# 1-Schematic.net
KiCad netlist of a schematic drawn in EasyEDA
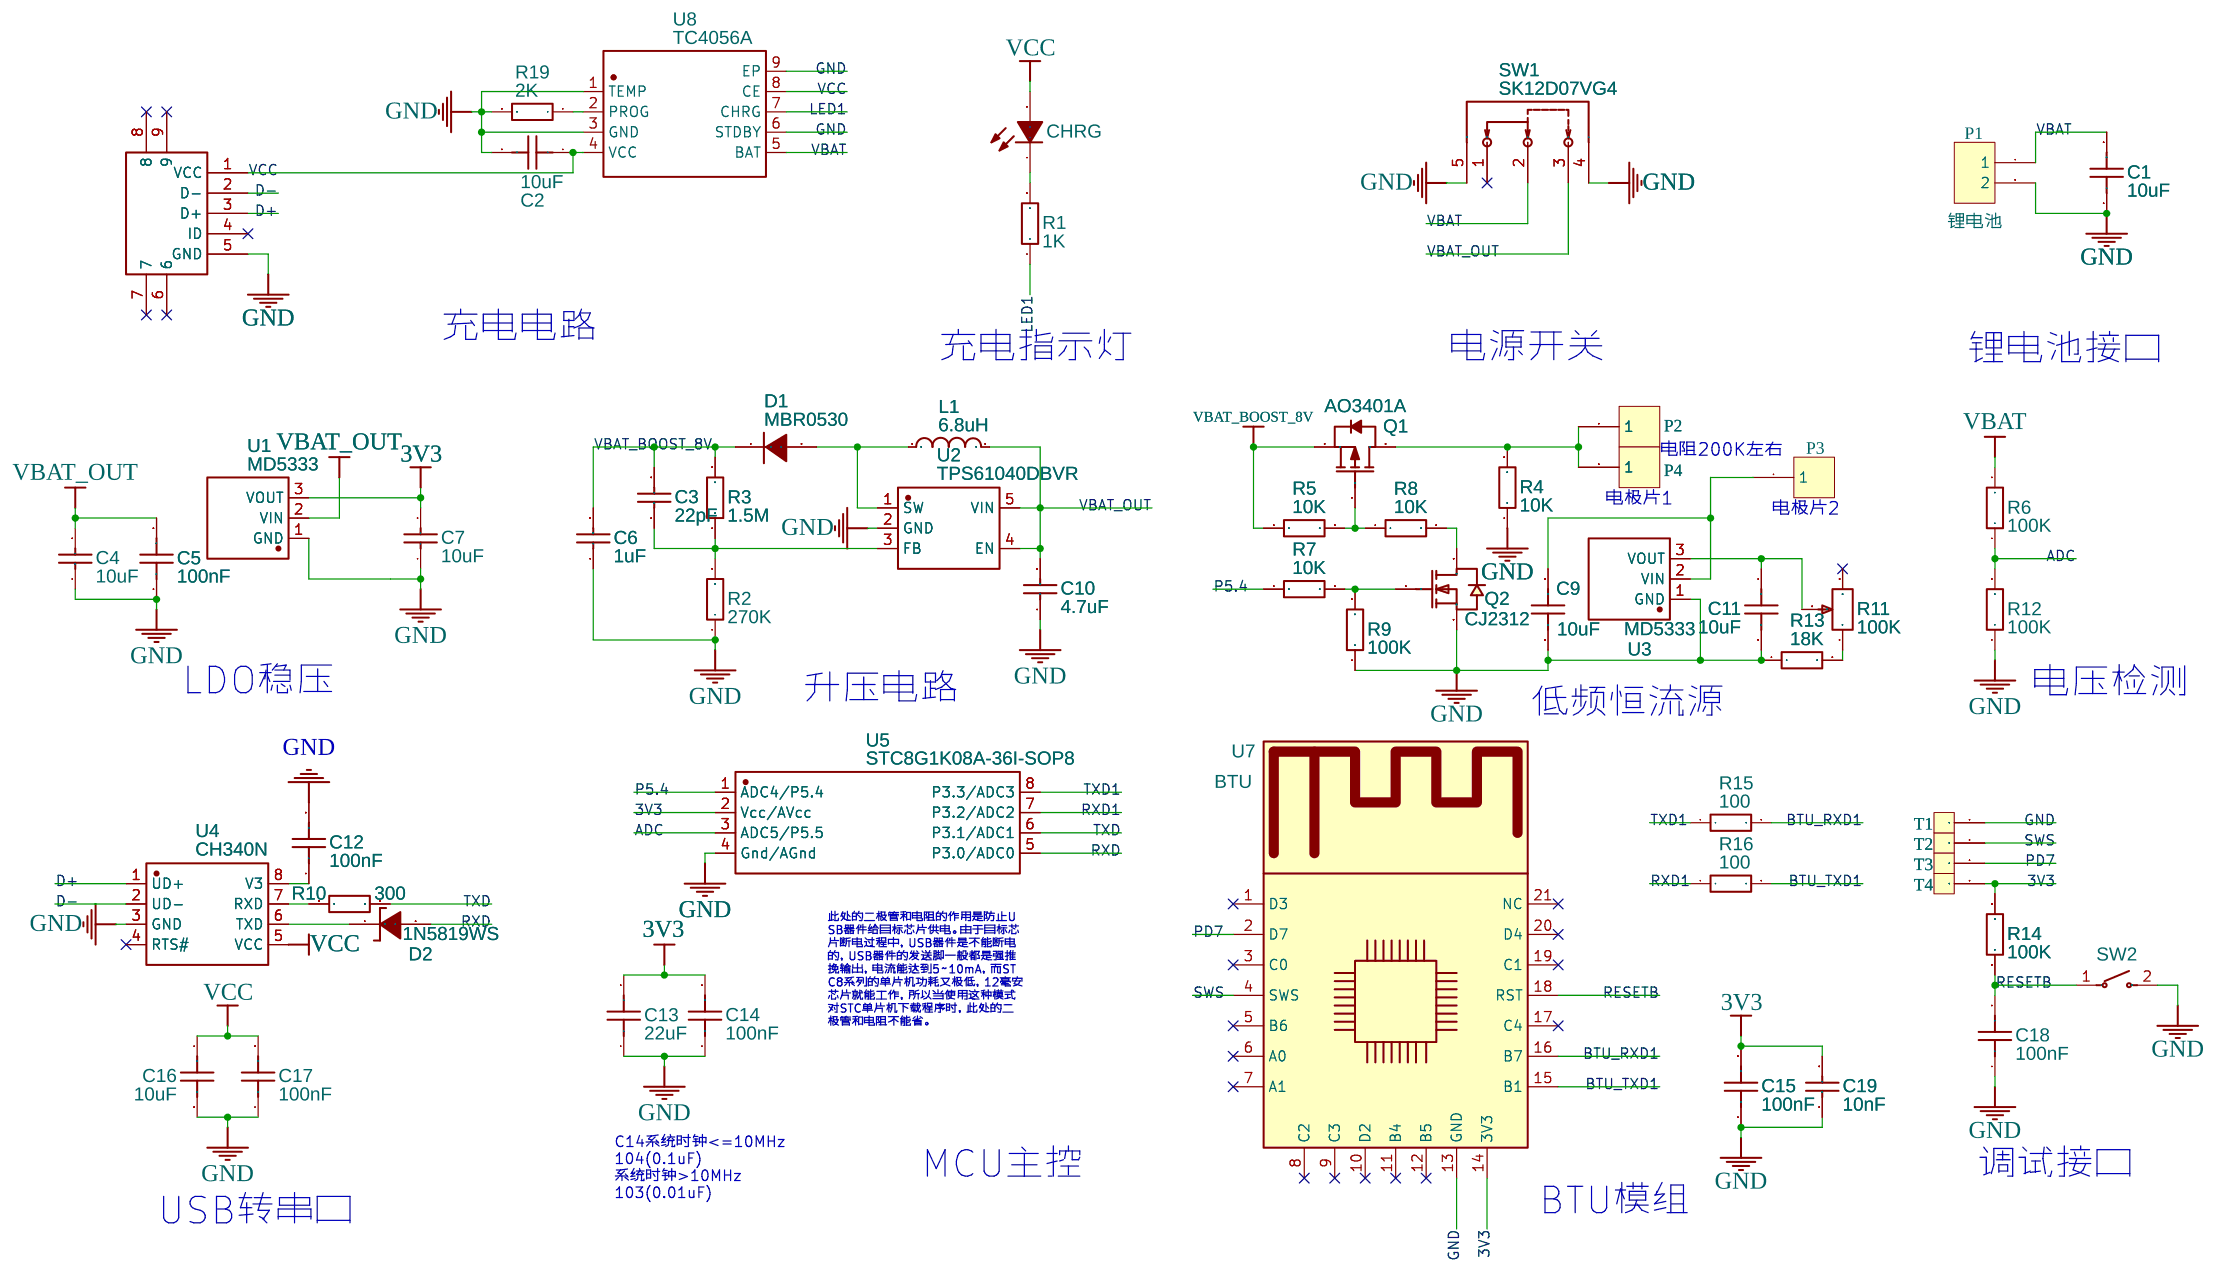
[diagram p0: schematic sheet]

(export (version "E")
  (design (tool "Eeschema 10.0.6"))
  (components
    (comp (ref "C1")
      (value "10uF")
      (fields
        (field (name "BOM_Manufacturer Part") "CL10A106KP8NNNC")
        (field (name "BOM_Supplier Part") "C19702")
      )
      (libsource (lib "") (part "CL10A106KP8NNNC"))
    )
    (comp (ref "C2")
      (value "10uF")
      (fields
        (field (name "BOM_Manufacturer Part") "CL10A106KP8NNNC")
        (field (name "BOM_Supplier Part") "C19702")
      )
      (libsource (lib "") (part "CL10A106KP8NNNC_2"))
    )
    (comp (ref "C3")
      (value "22pF")
      (fields
        (field (name "BOM_Manufacturer Part") "CC0603JRNPO9BN220")
        (field (name "BOM_Supplier Part") "C105620")
      )
      (libsource (lib "") (part "CC0603JRNPO9BN220"))
    )
    (comp (ref "C4")
      (value "10uF")
      (fields
        (field (name "BOM_Manufacturer Part") "CC0603MRX5R6BB106")
        (field (name "BOM_Supplier Part") "C109453")
      )
      (libsource (lib "") (part "CC0603MRX5R6BB106"))
    )
    (comp (ref "C5")
      (value "100nF")
      (fields
        (field (name "BOM_Manufacturer Part") "0603F104Z500")
        (field (name "BOM_Supplier Part") "C83060")
      )
      (libsource (lib "") (part "0603F104Z500"))
    )
    (comp (ref "C6")
      (value "1uF")
      (fields
        (field (name "BOM_Manufacturer Part") "CL10A105KO8NNNC")
        (field (name "BOM_Supplier Part") "C1592")
      )
      (libsource (lib "") (part "CL10A105KO8NNNC"))
    )
    (comp (ref "C7")
      (value "10uF")
      (fields
        (field (name "BOM_Manufacturer Part") "CC0603MRX5R6BB106")
        (field (name "BOM_Supplier Part") "C109453")
      )
      (libsource (lib "") (part "CC0603MRX5R6BB106"))
    )
    (comp (ref "C9")
      (value "10uF")
      (fields
        (field (name "BOM_Manufacturer Part") "CL10A106KP8NNNC")
        (field (name "BOM_Supplier Part") "C19702")
      )
      (libsource (lib "") (part "CL10A106KP8NNNC_1"))
    )
    (comp (ref "C10")
      (value "4.7uF")
      (fields
        (field (name "BOM_Manufacturer Part") "CL10A475KP8NNNC")
        (field (name "BOM_Supplier Part") "C1705")
      )
      (libsource (lib "") (part "CL10A475KP8NNNC"))
    )
    (comp (ref "C11")
      (value "10uF")
      (fields
        (field (name "BOM_Manufacturer Part") "CL10A106KP8NNNC")
        (field (name "BOM_Supplier Part") "C19702")
      )
      (libsource (lib "") (part "CL10A106KP8NNNC_1"))
    )
    (comp (ref "C12")
      (value "100nF")
      (fields
        (field (name "BOM_Manufacturer Part") "CC0603KRX7R9BB104")
        (field (name "BOM_Supplier Part") "C14663")
      )
      (libsource (lib "") (part "CC0603KRX7R9BB104"))
    )
    (comp (ref "C13")
      (value "22uF")
      (fields
        (field (name "BOM_Manufacturer Part") "CL10A226MQ8NRNC")
        (field (name "BOM_Supplier Part") "C59461")
      )
      (libsource (lib "") (part "CL10A226MQ8NRNC"))
    )
    (comp (ref "C14")
      (value "100nF")
      (fields
        (field (name "BOM_Manufacturer Part") "CC0603KRX7R9BB104")
        (field (name "BOM_Supplier Part") "C14663")
      )
      (libsource (lib "") (part "CC0603KRX7R9BB104"))
    )
    (comp (ref "C15")
      (value "100nF")
      (fields
        (field (name "BOM_Manufacturer Part") "CC0603KRX7R9BB104")
        (field (name "BOM_Supplier Part") "C14663")
      )
      (libsource (lib "") (part "CC0603KRX7R9BB104"))
    )
    (comp (ref "C16")
      (value "10uF")
      (fields
        (field (name "BOM_Manufacturer Part") "CL10A106KP8NNNC")
        (field (name "BOM_Supplier Part") "C19702")
      )
      (libsource (lib "") (part "CL10A106KP8NNNC_1"))
    )
    (comp (ref "C17")
      (value "100nF")
      (fields
        (field (name "BOM_Manufacturer Part") "CC0603KRX7R9BB104")
        (field (name "BOM_Supplier Part") "C14663")
      )
      (libsource (lib "") (part "CC0603KRX7R9BB104"))
    )
    (comp (ref "C18")
      (value "100nF")
      (fields
        (field (name "BOM_Manufacturer Part") "CC0603KRX7R9BB104")
        (field (name "BOM_Supplier Part") "C14663")
      )
      (libsource (lib "") (part "CC0603KRX7R9BB104"))
    )
    (comp (ref "C19")
      (value "10nF")
      (fields
        (field (name "BOM_Manufacturer Part") "CC0603KRX7R9BB103")
        (field (name "BOM_Supplier Part") "C100042")
      )
      (libsource (lib "") (part "CC0603KRX7R9BB103"))
    )
    (comp (ref "CHRG")
      (value "19-21SURC/S530-A2/TR8")
      (fields (field (name "BOM_Supplier Part") "C72045"))
      (libsource (lib "") (part "19-21SURC/S530-A2/TR8"))
    )
    (comp (ref "D1")
      (value "MBR0530")
      (fields (field (name "BOM_Supplier Part") "C475718"))
      (libsource (lib "") (part "MBR0530_C475718"))
    )
    (comp (ref "D2")
      (value "1N5819WS")
      (fields (field (name "BOM_Supplier Part") "C191023"))
      (libsource (lib "") (part "1N5819WS"))
    )
    (comp (ref "L1")
      (value "6.8uH")
      (fields
        (field (name "BOM_Manufacturer Part") "CDRH3D23NP-6R8PC")
        (field (name "BOM_Supplier Part") "C323532")
      )
      (libsource (lib "") (part "CDRH3D23NP-6R8PC"))
    )
    (comp (ref "P1") (value "锂电池") (libsource (lib "") (part "Unknown_1010_-650")))
    (comp (ref "P2") (value "CON1") (libsource (lib "") (part "Unknown_825_-520")))
    (comp (ref "P3") (value "CON1") (libsource (lib "") (part "Unknown_911_-495")))
    (comp (ref "P4") (value "CON1") (libsource (lib "") (part "Unknown_825_-500")))
    (comp (ref "Q1")
      (value "AO3401A")
      (fields (field (name "BOM_Supplier Part") "C15127"))
      (libsource (lib "") (part "AO3401A"))
    )
    (comp (ref "Q2")
      (value "CJ2312")
      (fields (field (name "BOM_Supplier Part") "C23521"))
      (libsource (lib "") (part "CJ2312"))
    )
    (comp (ref "R1")
      (value "1K")
      (fields
        (field (name "BOM_Manufacturer Part") "RS-03K1001FT")
        (field (name "BOM_Supplier Part") "C115325")
      )
      (libsource (lib "") (part "RS-03K1001FT"))
    )
    (comp (ref "R2")
      (value "270K")
      (fields
        (field (name "BOM_Manufacturer Part") "0603WAF2703T5E")
        (field (name "BOM_Supplier Part") "C22965")
      )
      (libsource (lib "") (part "0603WAF2703T5E"))
    )
    (comp (ref "R3")
      (value "1.5M")
      (fields
        (field (name "BOM_Manufacturer Part") "0603WAF1504T5E")
        (field (name "BOM_Supplier Part") "C4172")
      )
      (libsource (lib "") (part "0603WAF1504T5E"))
    )
    (comp (ref "R4")
      (value "10K")
      (fields
        (field (name "BOM_Manufacturer Part") "RS-03K103JT")
        (field (name "BOM_Supplier Part") "C73809")
      )
      (libsource (lib "") (part "RS-03K103JT_1"))
    )
    (comp (ref "R5")
      (value "10K")
      (fields
        (field (name "BOM_Manufacturer Part") "RS-03K103JT")
        (field (name "BOM_Supplier Part") "C73809")
      )
      (libsource (lib "") (part "RS-03K103JT"))
    )
    (comp (ref "R6")
      (value "100K")
      (fields
        (field (name "BOM_Manufacturer Part") "RC0603FR-07100KL")
        (field (name "BOM_Supplier Part") "C14675")
      )
      (libsource (lib "") (part "RC0603FR-07100KL"))
    )
    (comp (ref "R7")
      (value "10K")
      (fields
        (field (name "BOM_Manufacturer Part") "RS-03K103JT")
        (field (name "BOM_Supplier Part") "C73809")
      )
      (libsource (lib "") (part "RS-03K103JT"))
    )
    (comp (ref "R8")
      (value "10K")
      (fields
        (field (name "BOM_Manufacturer Part") "RS-03K103JT")
        (field (name "BOM_Supplier Part") "C73809")
      )
      (libsource (lib "") (part "RS-03K103JT"))
    )
    (comp (ref "R9")
      (value "100K")
      (fields
        (field (name "BOM_Manufacturer Part") "RC0603FR-07100KL")
        (field (name "BOM_Supplier Part") "C14675")
      )
      (libsource (lib "") (part "RC0603FR-07100KL"))
    )
    (comp (ref "R10")
      (value "300")
      (fields
        (field (name "BOM_Manufacturer Part") "0603WAF3000T5E")
        (field (name "BOM_Supplier Part") "C23025")
      )
      (libsource (lib "") (part "0603WAF3000T5E"))
    )
    (comp (ref "R11")
      (value "100K")
      (fields
        (field (name "BOM_Manufacturer Part") "VG039NCHXTB104")
        (field (name "BOM_Supplier Part") "C128545")
      )
      (libsource (lib "") (part "VG039NCHXTB104"))
    )
    (comp (ref "R12")
      (value "100K")
      (fields
        (field (name "BOM_Manufacturer Part") "RC0603FR-07100KL")
        (field (name "BOM_Supplier Part") "C14675")
      )
      (libsource (lib "") (part "RC0603FR-07100KL"))
    )
    (comp (ref "R13")
      (value "18K")
      (fields
        (field (name "BOM_Manufacturer Part") "WR06X1502FTL")
        (field (name "BOM_Supplier Part") "C163863")
      )
      (libsource (lib "") (part "WR06X1502FTL"))
    )
    (comp (ref "R14")
      (value "100K")
      (fields
        (field (name "BOM_Manufacturer Part") "RC0603FR-07100KL")
        (field (name "BOM_Supplier Part") "C14675")
      )
      (libsource (lib "") (part "RC0603FR-07100KL"))
    )
    (comp (ref "R15")
      (value "100")
      (fields
        (field (name "BOM_Manufacturer Part") "0603WAJ0101T5E")
        (field (name "BOM_Supplier Part") "C25201")
      )
      (libsource (lib "") (part "0603WAJ0101T5E"))
    )
    (comp (ref "R16")
      (value "100")
      (fields
        (field (name "BOM_Manufacturer Part") "0603WAJ0101T5E")
        (field (name "BOM_Supplier Part") "C25201")
      )
      (libsource (lib "") (part "0603WAJ0101T5E"))
    )
    (comp (ref "R19")
      (value "2K")
      (fields
        (field (name "BOM_Manufacturer Part") "0603WAJ0202T5E")
        (field (name "BOM_Supplier Part") "C25590")
      )
      (libsource (lib "") (part "0603WAJ0202T5E"))
    )
    (comp (ref "SW1")
      (value "SK12D07VG4")
      (fields (field (name "BOM_Supplier Part") "C393937"))
      (libsource (lib "") (part "SK12D07VG4"))
    )
    (comp (ref "SW2")
      (value "TS-1088R-02026")
      (fields (field (name "BOM_Supplier Part") "C455280"))
      (libsource (lib "") (part "TS-1088R-02026"))
    )
    (comp (ref "T1") (value "TP") (libsource (lib "") (part "Unknown_985_-315")))
    (comp (ref "T2") (value "TP") (libsource (lib "") (part "Unknown_985_-305")))
    (comp (ref "T3") (value "TP") (libsource (lib "") (part "Unknown_985_-295")))
    (comp (ref "T4") (value "TP") (libsource (lib "") (part "Unknown_985_-285")))
    (comp (ref "U1")
      (value "MD5333")
      (fields (field (name "BOM_Supplier Part") "C2827936"))
      (libsource (lib "") (part "MD5333"))
    )
    (comp (ref "U2")
      (value "TPS61040DBVR")
      (fields (field (name "BOM_Supplier Part") "C7722"))
      (libsource (lib "") (part "TPS61040DBVR"))
    )
    (comp (ref "U3")
      (value "MD5333")
      (fields (field (name "BOM_Supplier Part") "C2827936"))
      (libsource (lib "") (part "MD5333"))
    )
    (comp (ref "U4")
      (value "CH340N")
      (fields (field (name "BOM_Supplier Part") "C506813"))
      (libsource (lib "") (part "CH340N"))
    )
    (comp (ref "U5")
      (value "STC8G1K08A-36I-SOP8")
      (fields (field (name "BOM_Supplier Part") "C915663"))
      (libsource (lib "") (part "STC8G1K08A-36I-SOP8"))
    )
    (comp (ref "U7") (value "BTU") (libsource (lib "") (part "BTU")))
    (comp (ref "U8")
      (value "TC4056A")
      (fields (field (name "BOM_Supplier Part") "C84051"))
      (libsource (lib "") (part "TC4056A"))
    )
    (comp (ref "USB1")
      (value "U254-051T-4BH23-S2S")
      (fields (field (name "BOM_Supplier Part") "C319163"))
      (libsource (lib "") (part "U254-051T-4BH23-S2S"))
    )
  )
  (nets
    (net (code "1") (name "/ADC") (class "Default")
      (node (ref "R12") (pin "2") (pinfunction "2_2") (pintype "unspecified"))
      (node (ref "R6") (pin "1") (pinfunction "1_1") (pintype "unspecified"))
      (node (ref "U5") (pin "3") (pinfunction "ADC5/P5.5_3") (pintype "unspecified"))
    )
    (net (code "2") (name "/BTU_RXD1") (class "Default")
      (node (ref "R15") (pin "2") (pinfunction "2_2") (pintype "input"))
      (node (ref "U7") (pin "16") (pinfunction "B7_16") (pintype "unspecified"))
    )
    (net (code "3") (name "/BTU_TXD1") (class "Default")
      (node (ref "R16") (pin "2") (pinfunction "2_2") (pintype "input"))
      (node (ref "U7") (pin "15") (pinfunction "B1_15") (pintype "unspecified"))
    )
    (net (code "4") (name "/D+") (class "Default")
      (node (ref "U4") (pin "1") (pinfunction "UD+_1") (pintype "unspecified"))
      (node (ref "USB1") (pin "3") (pinfunction "D+_3") (pintype "unspecified"))
    )
    (net (code "5") (name "/D-") (class "Default")
      (node (ref "U4") (pin "2") (pinfunction "UD-_2") (pintype "unspecified"))
      (node (ref "USB1") (pin "2") (pinfunction "D-_2") (pintype "unspecified"))
    )
    (net (code "6") (name "/LED1") (class "Default")
      (node (ref "R1") (pin "1") (pinfunction "1_1") (pintype "input"))
      (node (ref "U8") (pin "7") (pinfunction "CHRG_7") (pintype "unspecified"))
    )
    (net (code "7") (name "/P5.4") (class "Default")
      (node (ref "R7") (pin "1") (pinfunction "1_1") (pintype "input"))
      (node (ref "U5") (pin "1") (pinfunction "ADC4/P5.4_1") (pintype "unspecified"))
    )
    (net (code "8") (name "/PD7") (class "Default")
      (node (ref "T3") (pin "1") (pinfunction "1_1") (pintype "unspecified"))
      (node (ref "U7") (pin "2") (pinfunction "D7_2") (pintype "unspecified"))
    )
    (net (code "9") (name "/RESETB") (class "Default")
      (node (ref "C18") (pin "2") (pinfunction "2_2") (pintype "unspecified"))
      (node (ref "R14") (pin "1") (pinfunction "1_1") (pintype "unspecified"))
      (node (ref "SW2") (pin "1") (pinfunction "1_1") (pintype "unspecified"))
      (node (ref "U7") (pin "18") (pinfunction "RST_18") (pintype "unspecified"))
    )
    (net (code "10") (name "/RXD") (class "Default")
      (node (ref "D2") (pin "2") (pinfunction "A_2") (pintype "unspecified"))
      (node (ref "U5") (pin "5") (pinfunction "P3.0/ADC0_5") (pintype "unspecified"))
    )
    (net (code "11") (name "/RXD1") (class "Default")
      (node (ref "R16") (pin "1") (pinfunction "1_1") (pintype "input"))
      (node (ref "U5") (pin "7") (pinfunction "P3.2/ADC2_7") (pintype "unspecified"))
    )
    (net (code "12") (name "/SWS") (class "Default")
      (node (ref "T2") (pin "1") (pinfunction "1_1") (pintype "unspecified"))
      (node (ref "U7") (pin "4") (pinfunction "SWS_4") (pintype "unspecified"))
    )
    (net (code "13") (name "/TXD") (class "Default")
      (node (ref "R10") (pin "2") (pinfunction "2_2") (pintype "input"))
      (node (ref "U5") (pin "6") (pinfunction "P3.1/ADC1_6") (pintype "unspecified"))
    )
    (net (code "14") (name "/TXD1") (class "Default")
      (node (ref "R15") (pin "1") (pinfunction "1_1") (pintype "input"))
      (node (ref "U5") (pin "8") (pinfunction "P3.3/ADC3_8") (pintype "unspecified"))
    )
    (net (code "15") (name "3V3") (class "Default")
      (node (ref "C13") (pin "2") (pinfunction "2_2") (pintype "unspecified"))
      (node (ref "C14") (pin "2") (pinfunction "2_2") (pintype "unspecified"))
      (node (ref "C15") (pin "2") (pinfunction "2_2") (pintype "unspecified"))
      (node (ref "C19") (pin "2") (pinfunction "2_2") (pintype "input"))
      (node (ref "C7") (pin "2") (pinfunction "2_2") (pintype "input"))
      (node (ref "R14") (pin "2") (pinfunction "2_2") (pintype "unspecified"))
      (node (ref "T4") (pin "1") (pinfunction "1_1") (pintype "unspecified"))
      (node (ref "U1") (pin "3") (pinfunction "VOUT_3") (pintype "unspecified"))
      (node (ref "U5") (pin "2") (pinfunction "Vcc/AVcc_2") (pintype "unspecified"))
      (node (ref "U7") (pin "14") (pinfunction "3V3_14") (pintype "unspecified"))
    )
    (net (code "16") (name "GND") (class "Default")
      (node (ref "C1") (pin "1") (pinfunction "1_1") (pintype "unspecified"))
      (node (ref "C10") (pin "1") (pinfunction "1_1") (pintype "input"))
      (node (ref "C11") (pin "2") (pinfunction "2_2") (pintype "unspecified"))
      (node (ref "C12") (pin "2") (pinfunction "2_2") (pintype "unspecified"))
      (node (ref "C13") (pin "1") (pinfunction "1_1") (pintype "unspecified"))
      (node (ref "C14") (pin "1") (pinfunction "1_1") (pintype "unspecified"))
      (node (ref "C15") (pin "1") (pinfunction "1_1") (pintype "unspecified"))
      (node (ref "C16") (pin "2") (pinfunction "2_2") (pintype "unspecified"))
      (node (ref "C17") (pin "1") (pinfunction "1_1") (pintype "unspecified"))
      (node (ref "C18") (pin "1") (pinfunction "1_1") (pintype "unspecified"))
      (node (ref "C19") (pin "1") (pinfunction "1_1") (pintype "input"))
      (node (ref "C2") (pin "2") (pinfunction "2_2") (pintype "unspecified"))
      (node (ref "C4") (pin "1") (pinfunction "1_1") (pintype "input"))
      (node (ref "C5") (pin "1") (pinfunction "1_1") (pintype "unspecified"))
      (node (ref "C6") (pin "1") (pinfunction "1_1") (pintype "input"))
      (node (ref "C7") (pin "1") (pinfunction "1_1") (pintype "input"))
      (node (ref "C9") (pin "2") (pinfunction "2_2") (pintype "unspecified"))
      (node (ref "P1") (pin "2") (pinfunction "2_2") (pintype "unspecified"))
      (node (ref "Q2") (pin "2") (pinfunction "S_2") (pintype "unspecified"))
      (node (ref "R12") (pin "1") (pinfunction "1_1") (pintype "unspecified"))
      (node (ref "R13") (pin "1") (pinfunction "1_1") (pintype "unspecified"))
      (node (ref "R19") (pin "2") (pinfunction "2_2") (pintype "input"))
      (node (ref "R2") (pin "1") (pinfunction "1_1") (pintype "input"))
      (node (ref "R4") (pin "1") (pinfunction "1_1") (pintype "input"))
      (node (ref "R9") (pin "1") (pinfunction "1_1") (pintype "unspecified"))
      (node (ref "SW1") (pin "4") (pinfunction "4_4") (pintype "unspecified"))
      (node (ref "SW1") (pin "5") (pinfunction "5_5") (pintype "unspecified"))
      (node (ref "SW2") (pin "2") (pinfunction "2_2") (pintype "unspecified"))
      (node (ref "T1") (pin "1") (pinfunction "1_1") (pintype "unspecified"))
      (node (ref "U1") (pin "1") (pinfunction "GND_1") (pintype "unspecified"))
      (node (ref "U2") (pin "2") (pinfunction "GND_2") (pintype "unspecified"))
      (node (ref "U3") (pin "1") (pinfunction "GND_1") (pintype "unspecified"))
      (node (ref "U4") (pin "3") (pinfunction "GND_3") (pintype "unspecified"))
      (node (ref "U5") (pin "4") (pinfunction "Gnd/AGnd_4") (pintype "unspecified"))
      (node (ref "U7") (pin "13") (pinfunction "GND_13") (pintype "unspecified"))
      (node (ref "U8") (pin "1") (pinfunction "TEMP_1") (pintype "unspecified"))
      (node (ref "U8") (pin "3") (pinfunction "GND_3") (pintype "unspecified"))
      (node (ref "U8") (pin "6") (pinfunction "STDBY_6") (pintype "unspecified"))
      (node (ref "U8") (pin "9") (pinfunction "EP_9") (pintype "unspecified"))
      (node (ref "USB1") (pin "5") (pinfunction "GND_5") (pintype "unspecified"))
    )
    (net (code "17") (name "Net-(CHRG--)") (class "Default")
      (node (ref "CHRG") (pin "1") (pinfunction "-_1") (pintype "input"))
      (node (ref "R1") (pin "2") (pinfunction "2_2") (pintype "input"))
    )
    (net (code "18") (name "Net-(D1-A)") (class "Default")
      (node (ref "D1") (pin "2") (pinfunction "A_2") (pintype "unspecified"))
      (node (ref "L1") (pin "1") (pinfunction "1_1") (pintype "unspecified"))
      (node (ref "U2") (pin "1") (pinfunction "SW_1") (pintype "unspecified"))
    )
    (net (code "19") (name "Net-(D2-C)") (class "Default")
      (node (ref "D2") (pin "1") (pinfunction "C_1") (pintype "unspecified"))
      (node (ref "U4") (pin "6") (pinfunction "TXD_6") (pintype "unspecified"))
    )
    (net (code "20") (name "Net-(Q1-D)") (class "Default")
      (node (ref "P2") (pin "1") (pinfunction "1_1") (pintype "unspecified"))
      (node (ref "P4") (pin "1") (pinfunction "1_1") (pintype "unspecified"))
      (node (ref "Q1") (pin "3") (pinfunction "D_3") (pintype "unspecified"))
      (node (ref "R4") (pin "2") (pinfunction "2_2") (pintype "input"))
    )
    (net (code "21") (name "Net-(Q1-G)") (class "Default")
      (node (ref "Q1") (pin "1") (pinfunction "G_1") (pintype "unspecified"))
      (node (ref "R5") (pin "2") (pinfunction "2_2") (pintype "input"))
      (node (ref "R8") (pin "1") (pinfunction "1_1") (pintype "input"))
    )
    (net (code "22") (name "Net-(Q2-D)") (class "Default")
      (node (ref "Q2") (pin "3") (pinfunction "D_3") (pintype "unspecified"))
      (node (ref "R8") (pin "2") (pinfunction "2_2") (pintype "input"))
    )
    (net (code "23") (name "Net-(Q2-G)") (class "Default")
      (node (ref "Q2") (pin "1") (pinfunction "G_1") (pintype "unspecified"))
      (node (ref "R7") (pin "2") (pinfunction "2_2") (pintype "input"))
      (node (ref "R9") (pin "2") (pinfunction "2_2") (pintype "unspecified"))
    )
    (net (code "24") (name "Net-(R11-Pad1)") (class "Default")
      (node (ref "R11") (pin "1") (pinfunction "1_1") (pintype "input"))
      (node (ref "R13") (pin "2") (pinfunction "2_2") (pintype "unspecified"))
    )
    (net (code "25") (name "Net-(U2-FB)") (class "Default")
      (node (ref "C3") (pin "1") (pinfunction "1_1") (pintype "input"))
      (node (ref "R2") (pin "2") (pinfunction "2_2") (pintype "input"))
      (node (ref "R3") (pin "1") (pinfunction "1_1") (pintype "input"))
      (node (ref "U2") (pin "3") (pinfunction "FB_3") (pintype "unspecified"))
    )
    (net (code "26") (name "Net-(U3-VIN)") (class "Default")
      (node (ref "C9") (pin "1") (pinfunction "1_1") (pintype "unspecified"))
      (node (ref "P3") (pin "1") (pinfunction "1_1") (pintype "unspecified"))
      (node (ref "U3") (pin "2") (pinfunction "VIN_2") (pintype "unspecified"))
    )
    (net (code "27") (name "Net-(U3-VOUT)") (class "Default")
      (node (ref "C11") (pin "1") (pinfunction "1_1") (pintype "unspecified"))
      (node (ref "R11") (pin "2") (pinfunction "2_2") (pintype "input"))
      (node (ref "U3") (pin "3") (pinfunction "VOUT_3") (pintype "unspecified"))
    )
    (net (code "28") (name "Net-(U4-RXD)") (class "Default")
      (node (ref "R10") (pin "1") (pinfunction "1_1") (pintype "input"))
      (node (ref "U4") (pin "7") (pinfunction "RXD_7") (pintype "unspecified"))
    )
    (net (code "29") (name "Net-(U4-V3)") (class "Default")
      (node (ref "C12") (pin "1") (pinfunction "1_1") (pintype "unspecified"))
      (node (ref "U4") (pin "8") (pinfunction "V3_8") (pintype "unspecified"))
    )
    (net (code "30") (name "Net-(U8-PROG)") (class "Default")
      (node (ref "R19") (pin "1") (pinfunction "1_1") (pintype "input"))
      (node (ref "U8") (pin "2") (pinfunction "PROG_2") (pintype "unspecified"))
    )
    (net (code "31") (name "VBAT") (class "Default")
      (node (ref "C1") (pin "2") (pinfunction "2_2") (pintype "unspecified"))
      (node (ref "P1") (pin "1") (pinfunction "1_1") (pintype "unspecified"))
      (node (ref "R6") (pin "2") (pinfunction "2_2") (pintype "unspecified"))
      (node (ref "SW1") (pin "2") (pinfunction "2_2") (pintype "unspecified"))
      (node (ref "U8") (pin "5") (pinfunction "BAT_5") (pintype "unspecified"))
    )
    (net (code "32") (name "VBAT_BOOST_8V") (class "Default")
      (node (ref "C3") (pin "2") (pinfunction "2_2") (pintype "input"))
      (node (ref "C6") (pin "2") (pinfunction "2_2") (pintype "input"))
      (node (ref "D1") (pin "1") (pinfunction "K_1") (pintype "unspecified"))
      (node (ref "Q1") (pin "2") (pinfunction "S_2") (pintype "unspecified"))
      (node (ref "R3") (pin "2") (pinfunction "2_2") (pintype "input"))
      (node (ref "R5") (pin "1") (pinfunction "1_1") (pintype "input"))
    )
    (net (code "33") (name "VBAT_OUT") (class "Default")
      (node (ref "C10") (pin "2") (pinfunction "2_2") (pintype "input"))
      (node (ref "C4") (pin "2") (pinfunction "2_2") (pintype "input"))
      (node (ref "C5") (pin "2") (pinfunction "2_2") (pintype "unspecified"))
      (node (ref "L1") (pin "2") (pinfunction "2_2") (pintype "unspecified"))
      (node (ref "SW1") (pin "3") (pinfunction "3_3") (pintype "unspecified"))
      (node (ref "U1") (pin "2") (pinfunction "VIN_2") (pintype "unspecified"))
      (node (ref "U2") (pin "4") (pinfunction "EN_4") (pintype "unspecified"))
      (node (ref "U2") (pin "5") (pinfunction "VIN_5") (pintype "unspecified"))
    )
    (net (code "34") (name "VCC") (class "Default")
      (node (ref "C16") (pin "1") (pinfunction "1_1") (pintype "unspecified"))
      (node (ref "C17") (pin "2") (pinfunction "2_2") (pintype "unspecified"))
      (node (ref "C2") (pin "1") (pinfunction "1_1") (pintype "unspecified"))
      (node (ref "CHRG") (pin "2") (pinfunction "+_2") (pintype "input"))
      (node (ref "U4") (pin "5") (pinfunction "VCC_5") (pintype "unspecified"))
      (node (ref "U8") (pin "4") (pinfunction "VCC_4") (pintype "unspecified"))
      (node (ref "U8") (pin "8") (pinfunction "CE_8") (pintype "unspecified"))
      (node (ref "USB1") (pin "1") (pinfunction "VCC_1") (pintype "unspecified"))
    )
    (net (code "35") (name "unconnected-(R11-Pad3)") (class "Default")
      (node (ref "R11") (pin "3") (pinfunction "3_3") (pintype "input+no_connect"))
    )
    (net (code "36") (name "unconnected-(SW1-Pad1)") (class "Default")
      (node (ref "SW1") (pin "1") (pinfunction "1_1") (pintype "unspecified+no_connect"))
    )
    (net (code "37") (name "unconnected-(U4-RTS#-Pad4)") (class "Default")
      (node (ref "U4") (pin "4") (pinfunction "RTS#_4") (pintype "unspecified+no_connect"))
    )
    (net (code "38") (name "unconnected-(U7-A0-Pad6)") (class "Default")
      (node (ref "U7") (pin "6") (pinfunction "A0_6") (pintype "unspecified+no_connect"))
    )
    (net (code "39") (name "unconnected-(U7-A1-Pad7)") (class "Default")
      (node (ref "U7") (pin "7") (pinfunction "A1_7") (pintype "unspecified+no_connect"))
    )
    (net (code "40") (name "unconnected-(U7-B4-Pad11)") (class "Default")
      (node (ref "U7") (pin "11") (pinfunction "B4_11") (pintype "unspecified+no_connect"))
    )
    (net (code "41") (name "unconnected-(U7-B5-Pad12)") (class "Default")
      (node (ref "U7") (pin "12") (pinfunction "B5_12") (pintype "unspecified+no_connect"))
    )
    (net (code "42") (name "unconnected-(U7-B6-Pad5)") (class "Default")
      (node (ref "U7") (pin "5") (pinfunction "B6_5") (pintype "unspecified+no_connect"))
    )
    (net (code "43") (name "unconnected-(U7-C0-Pad3)") (class "Default")
      (node (ref "U7") (pin "3") (pinfunction "C0_3") (pintype "unspecified+no_connect"))
    )
    (net (code "44") (name "unconnected-(U7-C1-Pad19)") (class "Default")
      (node (ref "U7") (pin "19") (pinfunction "C1_19") (pintype "unspecified+no_connect"))
    )
    (net (code "45") (name "unconnected-(U7-C2-Pad8)") (class "Default")
      (node (ref "U7") (pin "8") (pinfunction "C2_8") (pintype "unspecified+no_connect"))
    )
    (net (code "46") (name "unconnected-(U7-C3-Pad9)") (class "Default")
      (node (ref "U7") (pin "9") (pinfunction "C3_9") (pintype "unspecified+no_connect"))
    )
    (net (code "47") (name "unconnected-(U7-C4-Pad17)") (class "Default")
      (node (ref "U7") (pin "17") (pinfunction "C4_17") (pintype "unspecified+no_connect"))
    )
    (net (code "48") (name "unconnected-(U7-D2-Pad10)") (class "Default")
      (node (ref "U7") (pin "10") (pinfunction "D2_10") (pintype "unspecified+no_connect"))
    )
    (net (code "49") (name "unconnected-(U7-D3-Pad1)") (class "Default")
      (node (ref "U7") (pin "1") (pinfunction "D3_1") (pintype "unspecified+no_connect"))
    )
    (net (code "50") (name "unconnected-(U7-D4-Pad20)") (class "Default")
      (node (ref "U7") (pin "20") (pinfunction "D4_20") (pintype "unspecified+no_connect"))
    )
    (net (code "51") (name "unconnected-(U7-NC-Pad21)") (class "Default")
      (node (ref "U7") (pin "21") (pinfunction "NC_21") (pintype "unspecified+no_connect"))
    )
    (net (code "52") (name "unconnected-(USB1-ID-Pad4)") (class "Default")
      (node (ref "USB1") (pin "4") (pinfunction "ID_4") (pintype "unspecified+no_connect"))
    )
    (net (code "53") (name "unconnected-(USB1-Pad6)") (class "Default")
      (node (ref "USB1") (pin "6") (pinfunction "6_6") (pintype "unspecified+no_connect"))
    )
    (net (code "54") (name "unconnected-(USB1-Pad7)") (class "Default")
      (node (ref "USB1") (pin "7") (pinfunction "7_7") (pintype "unspecified+no_connect"))
    )
    (net (code "55") (name "unconnected-(USB1-Pad8)") (class "Default")
      (node (ref "USB1") (pin "8") (pinfunction "8_8") (pintype "unspecified+no_connect"))
    )
    (net (code "56") (name "unconnected-(USB1-Pad9)") (class "Default")
      (node (ref "USB1") (pin "9") (pinfunction "9_9") (pintype "unspecified+no_connect"))
    )
  )
)
